# MainBoard_V1_1.net
KiCad netlist of a schematic drawn in EAGLE
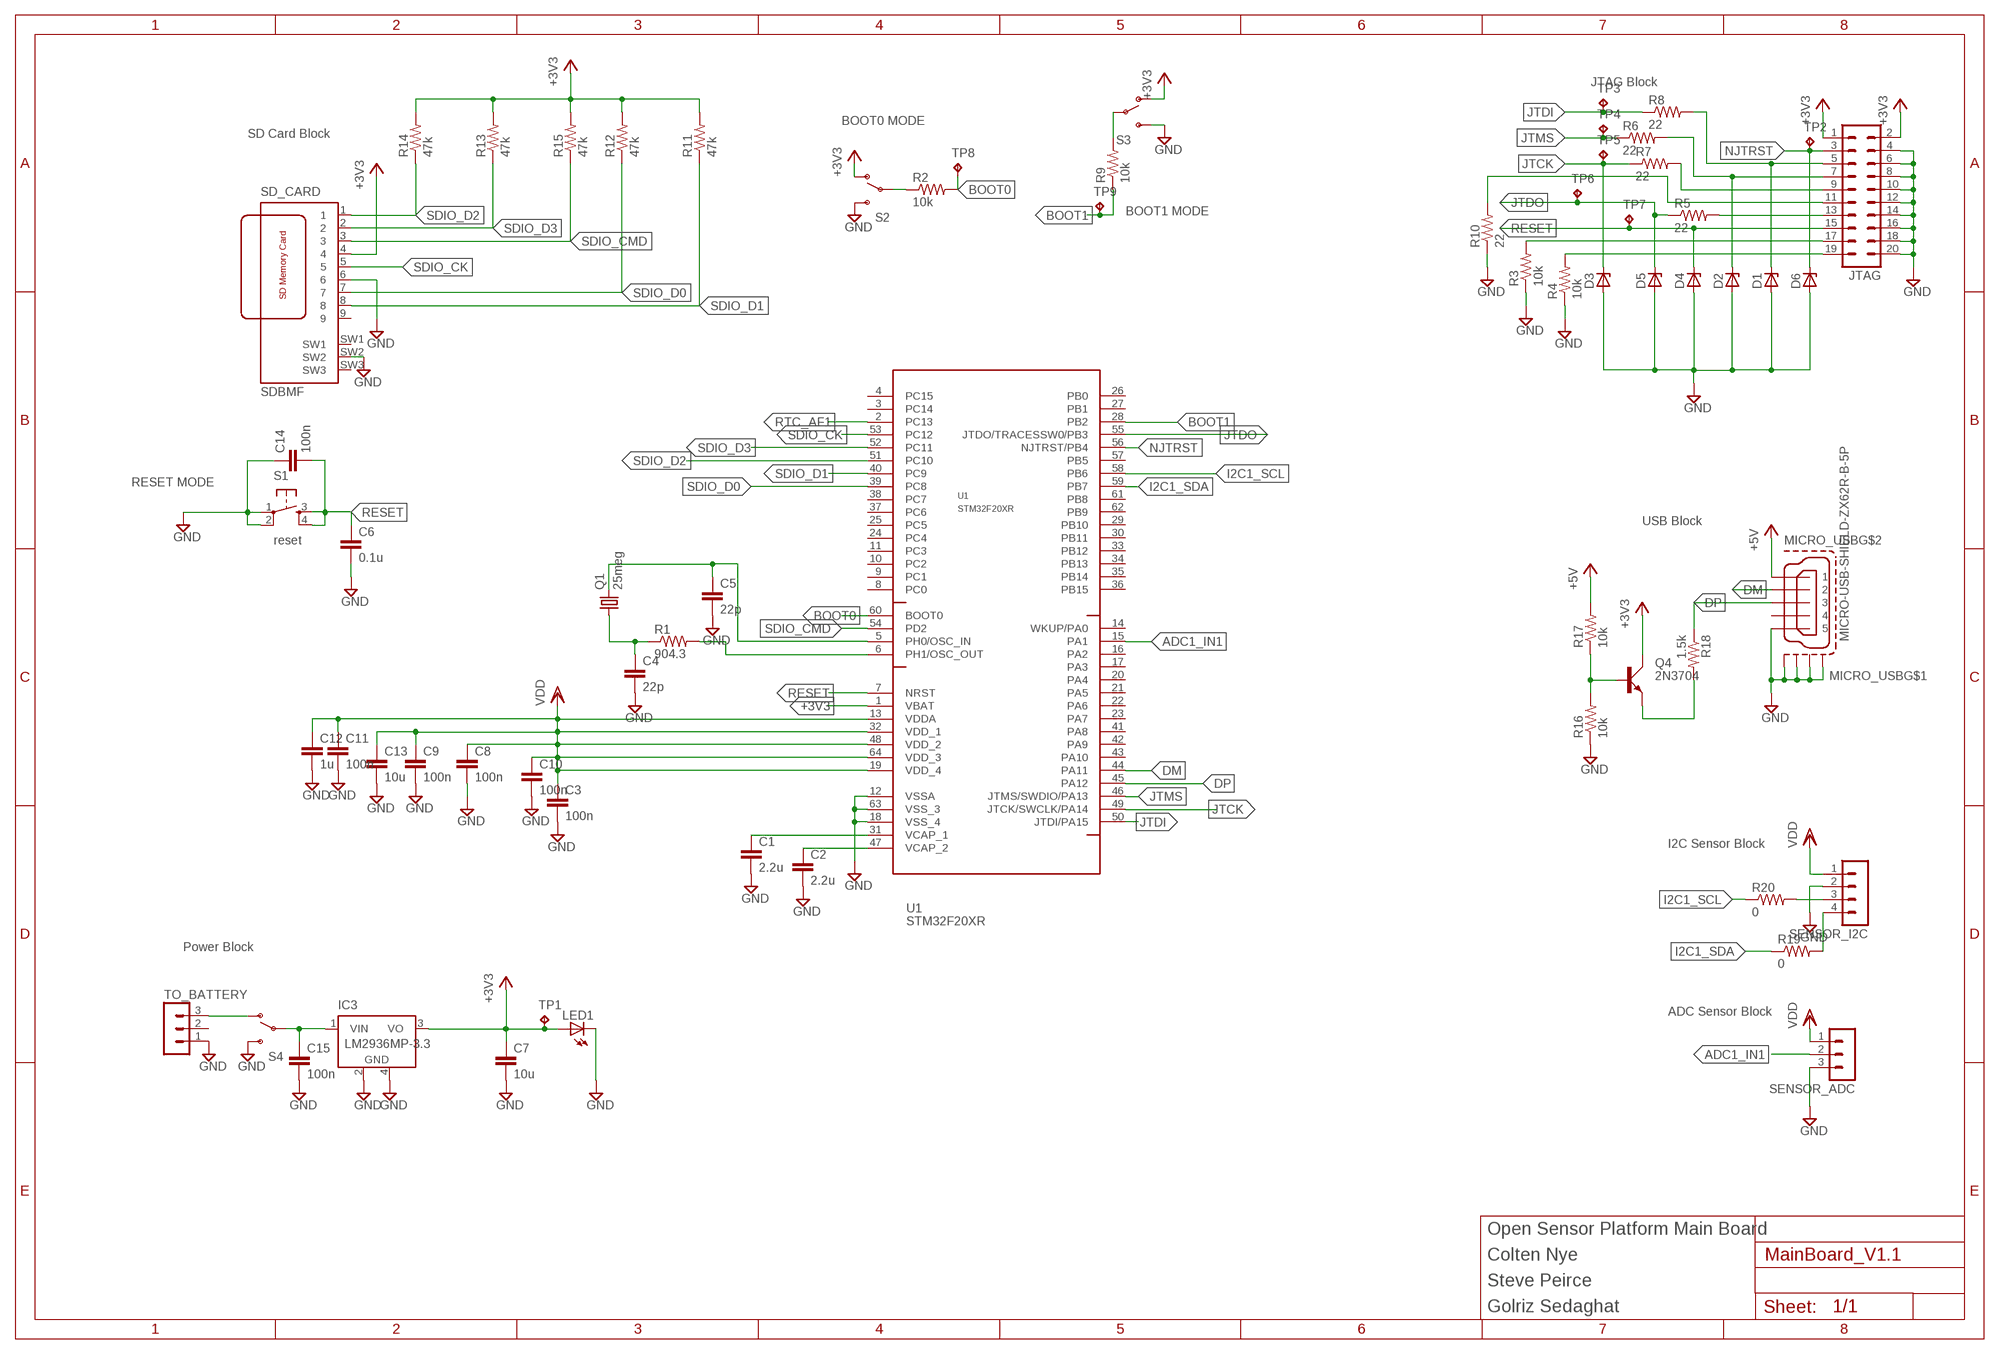
[diagram p0: schematic, sheet 1]

(export (version "E")
  (design (tool "Eeschema 10.0.6"))
  (components
    (comp (ref "C1")
      (value "2.2u")
      (footprint "eagle-import:C0805")
      (libsource (lib "eagle-import") (part "C-EUC0805"))
    )
    (comp (ref "C2")
      (value "2.2u")
      (footprint "eagle-import:C0805")
      (libsource (lib "eagle-import") (part "C-EUC0805"))
    )
    (comp (ref "C3")
      (value "100n")
      (footprint "eagle-import:C0805")
      (libsource (lib "eagle-import") (part "C-EUC0805"))
    )
    (comp (ref "C4")
      (value "22p")
      (footprint "eagle-import:C0805")
      (libsource (lib "eagle-import") (part "C-EUC0805"))
    )
    (comp (ref "C5")
      (value "22p")
      (footprint "eagle-import:C0805")
      (libsource (lib "eagle-import") (part "C-EUC0805"))
    )
    (comp (ref "C6")
      (value "0.1u")
      (footprint "eagle-import:C0805")
      (libsource (lib "eagle-import") (part "C-EUC0805"))
    )
    (comp (ref "C7")
      (value "10u")
      (footprint "eagle-import:C0805")
      (libsource (lib "eagle-import") (part "C-EUC0805"))
    )
    (comp (ref "C8")
      (value "100n")
      (footprint "eagle-import:C0805")
      (libsource (lib "eagle-import") (part "C-EUC0805"))
    )
    (comp (ref "C9")
      (value "100n")
      (footprint "eagle-import:C0805")
      (libsource (lib "eagle-import") (part "C-EUC0805"))
    )
    (comp (ref "C10")
      (value "100n")
      (footprint "eagle-import:C0805")
      (libsource (lib "eagle-import") (part "C-EUC0805"))
    )
    (comp (ref "C11")
      (value "100n")
      (footprint "eagle-import:C0805")
      (libsource (lib "eagle-import") (part "C-EUC0805"))
    )
    (comp (ref "C12")
      (value "1u")
      (footprint "eagle-import:C0805")
      (libsource (lib "eagle-import") (part "C-EUC0805"))
    )
    (comp (ref "C13")
      (value "10u")
      (footprint "eagle-import:C0805")
      (libsource (lib "eagle-import") (part "C-EUC0805"))
    )
    (comp (ref "C14")
      (value "100n")
      (footprint "eagle-import:C0805")
      (libsource (lib "eagle-import") (part "C-EUC0805"))
    )
    (comp (ref "C15")
      (value "100n")
      (footprint "eagle-import:C0805")
      (libsource (lib "eagle-import") (part "C-EUC0805"))
    )
    (comp (ref "D1")
      (value "ZENER-DIODEZD-5")
      (footprint "eagle-import:ZDIO-5")
      (libsource (lib "eagle-import") (part "ZENER-DIODEZD-5"))
    )
    (comp (ref "D2")
      (value "ZENER-DIODEZD-5")
      (footprint "eagle-import:ZDIO-5")
      (libsource (lib "eagle-import") (part "ZENER-DIODEZD-5"))
    )
    (comp (ref "D3")
      (value "ZENER-DIODEZD-5")
      (footprint "eagle-import:ZDIO-5")
      (libsource (lib "eagle-import") (part "ZENER-DIODEZD-5"))
    )
    (comp (ref "D4")
      (value "ZENER-DIODEZD-5")
      (footprint "eagle-import:ZDIO-5")
      (libsource (lib "eagle-import") (part "ZENER-DIODEZD-5"))
    )
    (comp (ref "D5")
      (value "ZENER-DIODEZD-5")
      (footprint "eagle-import:ZDIO-5")
      (libsource (lib "eagle-import") (part "ZENER-DIODEZD-5"))
    )
    (comp (ref "D6")
      (value "ZENER-DIODEZD-5")
      (footprint "eagle-import:ZDIO-5")
      (libsource (lib "eagle-import") (part "ZENER-DIODEZD-5"))
    )
    (comp (ref "IC3")
      (value "LM2936MP-3.3")
      (footprint "eagle-import:SOT223")
      (fields (field (name "MF") "NATIONAL SEMICONDUCTOR") (field (name "MPN") "LM2936MP-3.3/NOPB"))
      (libsource (lib "eagle-import") (part "LM2936MP?-3.3"))
    )
    (comp (ref "JTAG")
      (value "MA10-2")
      (footprint "eagle-import:MA10-2")
      (libsource (lib "eagle-import") (part "MA10-2"))
    )
    (comp (ref "LED1")
      (value "LEDSML0805")
      (footprint "eagle-import:SML0805")
      (libsource (lib "eagle-import") (part "LEDSML0805"))
    )
    (comp (ref "MICRO_USB")
      (value "MICRO-USB-SHIELD-ZX62R-B-5P")
      (footprint "eagle-import:ZX62R-B-5P")
      (libsource (lib "eagle-import") (part "MICRO-USB-SHIELD-ZX62R-B-5P"))
    )
    (comp (ref "Q1")
      (value "25meg")
      (footprint "eagle-import:HC49_S")
      (libsource (lib "eagle-import") (part "CRYSTALHC49S"))
    )
    (comp (ref "Q4")
      (value "2N3704")
      (footprint "eagle-import:TO92C")
      (libsource (lib "eagle-import") (part "2N3704"))
    )
    (comp (ref "R1")
      (value "904.3")
      (footprint "eagle-import:R0805")
      (libsource (lib "eagle-import") (part "R-US_R0805"))
    )
    (comp (ref "R2")
      (value "10k")
      (footprint "eagle-import:R0805")
      (libsource (lib "eagle-import") (part "R-US_R0805"))
    )
    (comp (ref "R3")
      (value "10k")
      (footprint "eagle-import:R0805")
      (libsource (lib "eagle-import") (part "R-US_R0805"))
    )
    (comp (ref "R4")
      (value "10k")
      (footprint "eagle-import:R0805")
      (libsource (lib "eagle-import") (part "R-US_R0805"))
    )
    (comp (ref "R5")
      (value "22")
      (footprint "eagle-import:R0805")
      (libsource (lib "eagle-import") (part "R-US_R0805"))
    )
    (comp (ref "R6")
      (value "22")
      (footprint "eagle-import:R0805")
      (libsource (lib "eagle-import") (part "R-US_R0805"))
    )
    (comp (ref "R7")
      (value "22")
      (footprint "eagle-import:R0805")
      (libsource (lib "eagle-import") (part "R-US_R0805"))
    )
    (comp (ref "R8")
      (value "22")
      (footprint "eagle-import:R0805")
      (libsource (lib "eagle-import") (part "R-US_R0805"))
    )
    (comp (ref "R9")
      (value "10k")
      (footprint "eagle-import:R0805")
      (libsource (lib "eagle-import") (part "R-US_R0805"))
    )
    (comp (ref "R10")
      (value "22")
      (footprint "eagle-import:R0805")
      (libsource (lib "eagle-import") (part "R-US_R0805"))
    )
    (comp (ref "R11")
      (value "47k")
      (footprint "eagle-import:R0805")
      (libsource (lib "eagle-import") (part "R-US_R0805"))
    )
    (comp (ref "R12")
      (value "47k")
      (footprint "eagle-import:R0805")
      (libsource (lib "eagle-import") (part "R-US_R0805"))
    )
    (comp (ref "R13")
      (value "47k")
      (footprint "eagle-import:R0805")
      (libsource (lib "eagle-import") (part "R-US_R0805"))
    )
    (comp (ref "R14")
      (value "47k")
      (footprint "eagle-import:R0805")
      (libsource (lib "eagle-import") (part "R-US_R0805"))
    )
    (comp (ref "R15")
      (value "47k")
      (footprint "eagle-import:R0805")
      (libsource (lib "eagle-import") (part "R-US_R0805"))
    )
    (comp (ref "R16")
      (value "10k")
      (footprint "eagle-import:R0805")
      (libsource (lib "eagle-import") (part "R-US_R0805"))
    )
    (comp (ref "R17")
      (value "10k")
      (footprint "eagle-import:R0805")
      (libsource (lib "eagle-import") (part "R-US_R0805"))
    )
    (comp (ref "R18")
      (value "1.5k")
      (footprint "eagle-import:R0805")
      (libsource (lib "eagle-import") (part "R-US_R0805"))
    )
    (comp (ref "R19")
      (value "0")
      (footprint "eagle-import:R0805")
      (libsource (lib "eagle-import") (part "R-US_R0805"))
    )
    (comp (ref "R20")
      (value "0")
      (footprint "eagle-import:R0805")
      (libsource (lib "eagle-import") (part "R-US_R0805"))
    )
    (comp (ref "S1")
      (value "reset")
      (footprint "eagle-import:TACTILE-SWITCH-SMD")
      (libsource (lib "eagle-import") (part "TAC_SWITCHSMD"))
    )
    (comp (ref "S2")
      (value "SWITCH-SPDT-SMD-A")
      (footprint "eagle-import:SWITCH-SPST-SMD-A")
      (libsource (lib "eagle-import") (part "SWITCH-SPDT-SMD-A"))
    )
    (comp (ref "S3")
      (value "SWITCH-SPDT-SMD-A")
      (footprint "eagle-import:SWITCH-SPST-SMD-A")
      (libsource (lib "eagle-import") (part "SWITCH-SPDT-SMD-A"))
    )
    (comp (ref "S4")
      (value "SWITCH-SPDT-SMD-A")
      (footprint "eagle-import:SWITCH-SPST-SMD-A")
      (libsource (lib "eagle-import") (part "SWITCH-SPDT-SMD-A"))
    )
    (comp (ref "SD_CARD")
      (value "SDBMF")
      (footprint "eagle-import:SDBMF-009XXBXX2")
      (libsource (lib "eagle-import") (part "SDBMF"))
    )
    (comp (ref "SENSOR_ADC")
      (value "MA03-1")
      (footprint "eagle-import:MA03-1")
      (libsource (lib "eagle-import") (part "MA03-1"))
    )
    (comp (ref "SENSOR_I2C")
      (value "MA04-1")
      (footprint "eagle-import:MA04-1")
      (libsource (lib "eagle-import") (part "MA04-1"))
    )
    (comp (ref "TO_BATTERY")
      (value "MA03-1")
      (footprint "eagle-import:MA03-1")
      (libsource (lib "eagle-import") (part "MA03-1"))
    )
    (comp (ref "TP1")
      (value "TPB1,27")
      (footprint "eagle-import:B1,27")
      (libsource (lib "eagle-import") (part "TPB1,27"))
    )
    (comp (ref "TP2")
      (value "TPB1,27")
      (footprint "eagle-import:B1,27")
      (libsource (lib "eagle-import") (part "TPB1,27"))
    )
    (comp (ref "TP3")
      (value "TPB1,27")
      (footprint "eagle-import:B1,27")
      (libsource (lib "eagle-import") (part "TPB1,27"))
    )
    (comp (ref "TP4")
      (value "TPB1,27")
      (footprint "eagle-import:B1,27")
      (libsource (lib "eagle-import") (part "TPB1,27"))
    )
    (comp (ref "TP5")
      (value "TPB1,27")
      (footprint "eagle-import:B1,27")
      (libsource (lib "eagle-import") (part "TPB1,27"))
    )
    (comp (ref "TP6")
      (value "TPB1,27")
      (footprint "eagle-import:B1,27")
      (libsource (lib "eagle-import") (part "TPB1,27"))
    )
    (comp (ref "TP7")
      (value "TPB1,27")
      (footprint "eagle-import:B1,27")
      (libsource (lib "eagle-import") (part "TPB1,27"))
    )
    (comp (ref "TP8")
      (value "TPB1,27")
      (footprint "eagle-import:B1,27")
      (libsource (lib "eagle-import") (part "TPB1,27"))
    )
    (comp (ref "TP9")
      (value "TPB1,27")
      (footprint "eagle-import:B1,27")
      (libsource (lib "eagle-import") (part "TPB1,27"))
    )
    (comp (ref "U1")
      (value "STM32F20XR")
      (footprint "eagle-import:LQFP64")
      (libsource (lib "eagle-import") (part "STM32F20XR"))
    )
  )
  (nets
    (net (code "1") (name "+3V3") (class "Default")
      (node (ref "C7") (pin "1") (pinfunction "1_1") (pintype "passive"))
      (node (ref "IC3") (pin "3") (pinfunction "VO_3") (pintype "passive"))
      (node (ref "JTAG") (pin "1") (pinfunction "1_1") (pintype "passive"))
      (node (ref "JTAG") (pin "2") (pinfunction "2_2") (pintype "passive"))
      (node (ref "LED1") (pin "A") (pinfunction "A_A") (pintype "passive"))
      (node (ref "Q4") (pin "C") (pinfunction "C_C") (pintype "passive"))
      (node (ref "R11") (pin "2") (pinfunction "2_2") (pintype "passive"))
      (node (ref "R12") (pin "2") (pinfunction "2_2") (pintype "passive"))
      (node (ref "R13") (pin "2") (pinfunction "2_2") (pintype "passive"))
      (node (ref "R14") (pin "2") (pinfunction "2_2") (pintype "passive"))
      (node (ref "R15") (pin "2") (pinfunction "2_2") (pintype "passive"))
      (node (ref "S2") (pin "1") (pinfunction "O_1") (pintype "passive"))
      (node (ref "S3") (pin "1") (pinfunction "O_1") (pintype "passive"))
      (node (ref "SD_CARD") (pin "4") (pinfunction "4_4") (pintype "passive"))
      (node (ref "TP1") (pin "TP") (pinfunction "TP_TP") (pintype "input"))
      (node (ref "U1") (pin "1") (pinfunction "VBAT_1") (pintype "power_in"))
    )
    (net (code "2") (name "+5V") (class "Default")
      (node (ref "MICRO_USB") (pin "1") (pinfunction "1_1") (pintype "input"))
      (node (ref "R17") (pin "2") (pinfunction "2_2") (pintype "passive"))
    )
    (net (code "3") (name "ADC1_IN1") (class "Default")
      (node (ref "SENSOR_ADC") (pin "2") (pinfunction "2_2") (pintype "passive"))
      (node (ref "U1") (pin "15") (pinfunction "PA1_15") (pintype "bidirectional"))
    )
    (net (code "4") (name "BOOT0") (class "Default")
      (node (ref "R2") (pin "2") (pinfunction "2_2") (pintype "passive"))
      (node (ref "TP8") (pin "TP") (pinfunction "TP_TP") (pintype "input"))
      (node (ref "U1") (pin "60") (pinfunction "BOOT0_60") (pintype "bidirectional"))
    )
    (net (code "5") (name "BOOT1") (class "Default")
      (node (ref "R9") (pin "1") (pinfunction "1_1") (pintype "passive"))
      (node (ref "TP9") (pin "TP") (pinfunction "TP_TP") (pintype "input"))
      (node (ref "U1") (pin "28") (pinfunction "PB2_28") (pintype "bidirectional"))
    )
    (net (code "6") (name "DM") (class "Default")
      (node (ref "MICRO_USB") (pin "2") (pinfunction "2_2") (pintype "input"))
      (node (ref "U1") (pin "44") (pinfunction "PA11_44") (pintype "bidirectional"))
    )
    (net (code "7") (name "DP") (class "Default")
      (node (ref "MICRO_USB") (pin "3") (pinfunction "3_3") (pintype "input"))
      (node (ref "R18") (pin "1") (pinfunction "1_1") (pintype "passive"))
      (node (ref "U1") (pin "45") (pinfunction "PA12_45") (pintype "bidirectional"))
    )
    (net (code "8") (name "GND") (class "Default")
      (node (ref "C1") (pin "2") (pinfunction "2_2") (pintype "passive"))
      (node (ref "C10") (pin "2") (pinfunction "2_2") (pintype "passive"))
      (node (ref "C11") (pin "2") (pinfunction "2_2") (pintype "passive"))
      (node (ref "C12") (pin "2") (pinfunction "2_2") (pintype "passive"))
      (node (ref "C13") (pin "2") (pinfunction "2_2") (pintype "passive"))
      (node (ref "C14") (pin "1") (pinfunction "1_1") (pintype "passive"))
      (node (ref "C15") (pin "2") (pinfunction "2_2") (pintype "passive"))
      (node (ref "C2") (pin "2") (pinfunction "2_2") (pintype "passive"))
      (node (ref "C3") (pin "2") (pinfunction "2_2") (pintype "passive"))
      (node (ref "C4") (pin "2") (pinfunction "2_2") (pintype "passive"))
      (node (ref "C5") (pin "2") (pinfunction "2_2") (pintype "passive"))
      (node (ref "C6") (pin "2") (pinfunction "2_2") (pintype "passive"))
      (node (ref "C7") (pin "2") (pinfunction "2_2") (pintype "passive"))
      (node (ref "C8") (pin "2") (pinfunction "2_2") (pintype "passive"))
      (node (ref "C9") (pin "2") (pinfunction "2_2") (pintype "passive"))
      (node (ref "D1") (pin "A") (pinfunction "A_A") (pintype "passive"))
      (node (ref "D2") (pin "A") (pinfunction "A_A") (pintype "passive"))
      (node (ref "D3") (pin "A") (pinfunction "A_A") (pintype "passive"))
      (node (ref "D4") (pin "A") (pinfunction "A_A") (pintype "passive"))
      (node (ref "D5") (pin "A") (pinfunction "A_A") (pintype "passive"))
      (node (ref "D6") (pin "A") (pinfunction "A_A") (pintype "passive"))
      (node (ref "IC3") (pin "2") (pinfunction "GND_2") (pintype "passive"))
      (node (ref "IC3") (pin "4") (pinfunction "GND_4") (pintype "passive"))
      (node (ref "JTAG") (pin "10") (pinfunction "10_10") (pintype "passive"))
      (node (ref "JTAG") (pin "12") (pinfunction "12_12") (pintype "passive"))
      (node (ref "JTAG") (pin "14") (pinfunction "14_14") (pintype "passive"))
      (node (ref "JTAG") (pin "16") (pinfunction "16_16") (pintype "passive"))
      (node (ref "JTAG") (pin "18") (pinfunction "18_18") (pintype "passive"))
      (node (ref "JTAG") (pin "20") (pinfunction "20_20") (pintype "passive"))
      (node (ref "JTAG") (pin "4") (pinfunction "4_4") (pintype "passive"))
      (node (ref "JTAG") (pin "6") (pinfunction "6_6") (pintype "passive"))
      (node (ref "JTAG") (pin "8") (pinfunction "8_8") (pintype "passive"))
      (node (ref "LED1") (pin "C") (pinfunction "C_C") (pintype "passive"))
      (node (ref "MICRO_USB") (pin "5") (pinfunction "5_5") (pintype "input"))
      (node (ref "MICRO_USB") (pin "M1") (pinfunction "S1_M1") (pintype "passive"))
      (node (ref "MICRO_USB") (pin "M2") (pinfunction "S2_M2") (pintype "passive"))
      (node (ref "MICRO_USB") (pin "M3") (pinfunction "S3_M3") (pintype "passive"))
      (node (ref "MICRO_USB") (pin "M4") (pinfunction "S4_M4") (pintype "passive"))
      (node (ref "R10") (pin "1") (pinfunction "1_1") (pintype "passive"))
      (node (ref "R16") (pin "1") (pinfunction "1_1") (pintype "passive"))
      (node (ref "R3") (pin "1") (pinfunction "1_1") (pintype "passive"))
      (node (ref "R4") (pin "1") (pinfunction "1_1") (pintype "passive"))
      (node (ref "S1") (pin "1") (pinfunction "1_1") (pintype "passive"))
      (node (ref "S1") (pin "2") (pinfunction "2_2") (pintype "passive"))
      (node (ref "S2") (pin "3") (pinfunction "S_3") (pintype "passive"))
      (node (ref "S3") (pin "3") (pinfunction "S_3") (pintype "passive"))
      (node (ref "S4") (pin "3") (pinfunction "S_3") (pintype "passive"))
      (node (ref "SD_CARD") (pin "6") (pinfunction "6_6") (pintype "passive"))
      (node (ref "SD_CARD") (pin "SW2") (pinfunction "SW2_SW2") (pintype "passive"))
      (node (ref "SENSOR_ADC") (pin "3") (pinfunction "3_3") (pintype "passive"))
      (node (ref "SENSOR_I2C") (pin "2") (pinfunction "2_2") (pintype "passive"))
      (node (ref "TO_BATTERY") (pin "1") (pinfunction "1_1") (pintype "passive"))
      (node (ref "U1") (pin "12") (pinfunction "VSSA_12") (pintype "power_in"))
      (node (ref "U1") (pin "18") (pinfunction "VSS_4_18") (pintype "power_in"))
      (node (ref "U1") (pin "63") (pinfunction "VSS_3_63") (pintype "power_in"))
    )
    (net (code "9") (name "I2C1_SCL") (class "Default")
      (node (ref "R20") (pin "1") (pinfunction "1_1") (pintype "passive"))
      (node (ref "U1") (pin "58") (pinfunction "PB6_58") (pintype "bidirectional"))
    )
    (net (code "10") (name "I2C1_SDA") (class "Default")
      (node (ref "R19") (pin "1") (pinfunction "1_1") (pintype "passive"))
      (node (ref "U1") (pin "59") (pinfunction "PB7_59") (pintype "bidirectional"))
    )
    (net (code "11") (name "JTCK") (class "Default")
      (node (ref "D3") (pin "C") (pinfunction "C_C") (pintype "passive"))
      (node (ref "R7") (pin "1") (pinfunction "1_1") (pintype "passive"))
      (node (ref "TP5") (pin "TP") (pinfunction "TP_TP") (pintype "input"))
      (node (ref "U1") (pin "49") (pinfunction "JTCK/SWCLK/PA14_49") (pintype "bidirectional"))
    )
    (net (code "12") (name "JTDI") (class "Default")
      (node (ref "R8") (pin "1") (pinfunction "1_1") (pintype "passive"))
      (node (ref "TP3") (pin "TP") (pinfunction "TP_TP") (pintype "input"))
      (node (ref "U1") (pin "50") (pinfunction "JTDI/PA15_50") (pintype "bidirectional"))
    )
    (net (code "13") (name "JTDO") (class "Default")
      (node (ref "D5") (pin "C") (pinfunction "C_C") (pintype "passive"))
      (node (ref "R5") (pin "1") (pinfunction "1_1") (pintype "passive"))
      (node (ref "TP6") (pin "TP") (pinfunction "TP_TP") (pintype "input"))
      (node (ref "U1") (pin "55") (pinfunction "JTDO/TRACESSW0/PB3_55") (pintype "bidirectional"))
    )
    (net (code "14") (name "JTMS") (class "Default")
      (node (ref "R6") (pin "1") (pinfunction "1_1") (pintype "passive"))
      (node (ref "TP4") (pin "TP") (pinfunction "TP_TP") (pintype "input"))
      (node (ref "U1") (pin "46") (pinfunction "JTMS/SWDIO/PA13_46") (pintype "bidirectional"))
    )
    (net (code "15") (name "NJTRST") (class "Default")
      (node (ref "D6") (pin "C") (pinfunction "C_C") (pintype "passive"))
      (node (ref "JTAG") (pin "3") (pinfunction "3_3") (pintype "passive"))
      (node (ref "TP2") (pin "TP") (pinfunction "TP_TP") (pintype "input"))
      (node (ref "U1") (pin "56") (pinfunction "NJTRST/PB4_56") (pintype "bidirectional"))
    )
    (net (code "16") (name "Net-(C4-Pad1)") (class "Default")
      (node (ref "C4") (pin "1") (pinfunction "1_1") (pintype "passive"))
      (node (ref "Q1") (pin "1") (pinfunction "1_1") (pintype "passive"))
      (node (ref "R1") (pin "1") (pinfunction "1_1") (pintype "passive"))
    )
    (net (code "17") (name "Net-(D1-PadC)") (class "Default")
      (node (ref "D1") (pin "C") (pinfunction "C_C") (pintype "passive"))
      (node (ref "JTAG") (pin "5") (pinfunction "5_5") (pintype "passive"))
      (node (ref "R8") (pin "2") (pinfunction "2_2") (pintype "passive"))
    )
    (net (code "18") (name "Net-(D2-PadC)") (class "Default")
      (node (ref "D2") (pin "C") (pinfunction "C_C") (pintype "passive"))
      (node (ref "JTAG") (pin "7") (pinfunction "7_7") (pintype "passive"))
      (node (ref "R6") (pin "2") (pinfunction "2_2") (pintype "passive"))
    )
    (net (code "19") (name "Net-(IC3-VIN)") (class "Default")
      (node (ref "C15") (pin "1") (pinfunction "1_1") (pintype "passive"))
      (node (ref "IC3") (pin "1") (pinfunction "VIN_1") (pintype "input"))
      (node (ref "S4") (pin "2") (pinfunction "P_2") (pintype "passive"))
    )
    (net (code "20") (name "Net-(JTAG-Pad9)") (class "Default")
      (node (ref "JTAG") (pin "9") (pinfunction "9_9") (pintype "passive"))
      (node (ref "R7") (pin "2") (pinfunction "2_2") (pintype "passive"))
    )
    (net (code "21") (name "Net-(JTAG-Pad11)") (class "Default")
      (node (ref "JTAG") (pin "11") (pinfunction "11_11") (pintype "passive"))
      (node (ref "R10") (pin "2") (pinfunction "2_2") (pintype "passive"))
    )
    (net (code "22") (name "Net-(JTAG-Pad13)") (class "Default")
      (node (ref "JTAG") (pin "13") (pinfunction "13_13") (pintype "passive"))
      (node (ref "R5") (pin "2") (pinfunction "2_2") (pintype "passive"))
    )
    (net (code "23") (name "Net-(JTAG-Pad17)") (class "Default")
      (node (ref "JTAG") (pin "17") (pinfunction "17_17") (pintype "passive"))
      (node (ref "R3") (pin "2") (pinfunction "2_2") (pintype "passive"))
    )
    (net (code "24") (name "Net-(JTAG-Pad19)") (class "Default")
      (node (ref "JTAG") (pin "19") (pinfunction "19_19") (pintype "passive"))
      (node (ref "R4") (pin "2") (pinfunction "2_2") (pintype "passive"))
    )
    (net (code "25") (name "Net-(Q4-PadB)") (class "Default")
      (node (ref "Q4") (pin "B") (pinfunction "B_B") (pintype "passive"))
      (node (ref "R16") (pin "2") (pinfunction "2_2") (pintype "passive"))
      (node (ref "R17") (pin "1") (pinfunction "1_1") (pintype "passive"))
    )
    (net (code "26") (name "Net-(Q4-PadE)") (class "Default")
      (node (ref "Q4") (pin "E") (pinfunction "E_E") (pintype "passive"))
      (node (ref "R18") (pin "2") (pinfunction "2_2") (pintype "passive"))
    )
    (net (code "27") (name "Net-(R19-Pad2)") (class "Default")
      (node (ref "R19") (pin "2") (pinfunction "2_2") (pintype "passive"))
      (node (ref "SENSOR_I2C") (pin "4") (pinfunction "4_4") (pintype "passive"))
    )
    (net (code "28") (name "Net-(R20-Pad2)") (class "Default")
      (node (ref "R20") (pin "2") (pinfunction "2_2") (pintype "passive"))
      (node (ref "SENSOR_I2C") (pin "3") (pinfunction "3_3") (pintype "passive"))
    )
    (net (code "29") (name "Net-(S2-P)") (class "Default")
      (node (ref "R2") (pin "1") (pinfunction "1_1") (pintype "passive"))
      (node (ref "S2") (pin "2") (pinfunction "P_2") (pintype "passive"))
    )
    (net (code "30") (name "Net-(S3-P)") (class "Default")
      (node (ref "R9") (pin "2") (pinfunction "2_2") (pintype "passive"))
      (node (ref "S3") (pin "2") (pinfunction "P_2") (pintype "passive"))
    )
    (net (code "31") (name "Net-(S4-O)") (class "Default")
      (node (ref "S4") (pin "1") (pinfunction "O_1") (pintype "passive"))
      (node (ref "TO_BATTERY") (pin "3") (pinfunction "3_3") (pintype "passive"))
    )
    (net (code "32") (name "Net-(U1-PH0{slash}OSC_IN)") (class "Default")
      (node (ref "C5") (pin "1") (pinfunction "1_1") (pintype "passive"))
      (node (ref "Q1") (pin "2") (pinfunction "2_2") (pintype "passive"))
      (node (ref "U1") (pin "5") (pinfunction "PH0/OSC_IN_5") (pintype "bidirectional"))
    )
    (net (code "33") (name "Net-(U1-PH1{slash}OSC_OUT)") (class "Default")
      (node (ref "R1") (pin "2") (pinfunction "2_2") (pintype "passive"))
      (node (ref "U1") (pin "6") (pinfunction "PH1/OSC_OUT_6") (pintype "bidirectional"))
    )
    (net (code "34") (name "Net-(U1-VCAP_1)") (class "Default")
      (node (ref "C1") (pin "1") (pinfunction "1_1") (pintype "passive"))
      (node (ref "U1") (pin "31") (pinfunction "VCAP_1_31") (pintype "power_in"))
    )
    (net (code "35") (name "Net-(U1-VCAP_2)") (class "Default")
      (node (ref "C2") (pin "1") (pinfunction "1_1") (pintype "passive"))
      (node (ref "U1") (pin "47") (pinfunction "VCAP_2_47") (pintype "power_in"))
    )
    (net (code "36") (name "RESET") (class "Default")
      (node (ref "C14") (pin "2") (pinfunction "2_2") (pintype "passive"))
      (node (ref "C6") (pin "1") (pinfunction "1_1") (pintype "passive"))
      (node (ref "D4") (pin "C") (pinfunction "C_C") (pintype "passive"))
      (node (ref "JTAG") (pin "15") (pinfunction "15_15") (pintype "passive"))
      (node (ref "S1") (pin "3") (pinfunction "3_3") (pintype "passive"))
      (node (ref "S1") (pin "4") (pinfunction "4_4") (pintype "passive"))
      (node (ref "TP7") (pin "TP") (pinfunction "TP_TP") (pintype "input"))
      (node (ref "U1") (pin "7") (pinfunction "NRST_7") (pintype "power_in"))
    )
    (net (code "37") (name "RTC_AF1") (class "Default")
      (node (ref "U1") (pin "2") (pinfunction "PC13_2") (pintype "bidirectional"))
    )
    (net (code "38") (name "SDIO_CK") (class "Default")
      (node (ref "SD_CARD") (pin "5") (pinfunction "5_5") (pintype "passive"))
      (node (ref "U1") (pin "53") (pinfunction "PC12_53") (pintype "bidirectional"))
    )
    (net (code "39") (name "SDIO_CMD") (class "Default")
      (node (ref "R15") (pin "1") (pinfunction "1_1") (pintype "passive"))
      (node (ref "SD_CARD") (pin "3") (pinfunction "3_3") (pintype "passive"))
      (node (ref "U1") (pin "54") (pinfunction "PD2_54") (pintype "bidirectional"))
    )
    (net (code "40") (name "SDIO_D0") (class "Default")
      (node (ref "R12") (pin "1") (pinfunction "1_1") (pintype "passive"))
      (node (ref "SD_CARD") (pin "7") (pinfunction "7_7") (pintype "passive"))
      (node (ref "U1") (pin "39") (pinfunction "PC8_39") (pintype "bidirectional"))
    )
    (net (code "41") (name "SDIO_D1") (class "Default")
      (node (ref "R11") (pin "1") (pinfunction "1_1") (pintype "passive"))
      (node (ref "SD_CARD") (pin "8") (pinfunction "8_8") (pintype "passive"))
      (node (ref "U1") (pin "40") (pinfunction "PC9_40") (pintype "bidirectional"))
    )
    (net (code "42") (name "SDIO_D2") (class "Default")
      (node (ref "R14") (pin "1") (pinfunction "1_1") (pintype "passive"))
      (node (ref "SD_CARD") (pin "1") (pinfunction "1_1") (pintype "passive"))
      (node (ref "U1") (pin "51") (pinfunction "PC10_51") (pintype "bidirectional"))
    )
    (net (code "43") (name "SDIO_D3") (class "Default")
      (node (ref "R13") (pin "1") (pinfunction "1_1") (pintype "passive"))
      (node (ref "SD_CARD") (pin "2") (pinfunction "2_2") (pintype "passive"))
      (node (ref "U1") (pin "52") (pinfunction "PC11_52") (pintype "bidirectional"))
    )
    (net (code "44") (name "VDD") (class "Default")
      (node (ref "C10") (pin "1") (pinfunction "1_1") (pintype "passive"))
      (node (ref "C11") (pin "1") (pinfunction "1_1") (pintype "passive"))
      (node (ref "C12") (pin "1") (pinfunction "1_1") (pintype "passive"))
      (node (ref "C13") (pin "1") (pinfunction "1_1") (pintype "passive"))
      (node (ref "C3") (pin "1") (pinfunction "1_1") (pintype "passive"))
      (node (ref "C8") (pin "1") (pinfunction "1_1") (pintype "passive"))
      (node (ref "C9") (pin "1") (pinfunction "1_1") (pintype "passive"))
      (node (ref "SENSOR_ADC") (pin "1") (pinfunction "1_1") (pintype "passive"))
      (node (ref "SENSOR_I2C") (pin "1") (pinfunction "1_1") (pintype "passive"))
      (node (ref "U1") (pin "13") (pinfunction "VDDA_13") (pintype "power_in"))
      (node (ref "U1") (pin "19") (pinfunction "VDD_4_19") (pintype "power_in"))
      (node (ref "U1") (pin "32") (pinfunction "VDD_1_32") (pintype "power_in"))
      (node (ref "U1") (pin "48") (pinfunction "VDD_2_48") (pintype "power_in"))
      (node (ref "U1") (pin "64") (pinfunction "VDD_3_64") (pintype "power_in"))
    )
    (net (code "45") (name "unconnected-(MICRO_USB-Pad4)") (class "Default")
      (node (ref "MICRO_USB") (pin "4") (pinfunction "4_4") (pintype "input"))
    )
    (net (code "46") (name "unconnected-(SD_CARD-Pad9)") (class "Default")
      (node (ref "SD_CARD") (pin "9") (pinfunction "9_9") (pintype "passive"))
    )
    (net (code "47") (name "unconnected-(SD_CARD-PadSW1)") (class "Default")
      (node (ref "SD_CARD") (pin "SW1") (pinfunction "SW1_SW1") (pintype "passive"))
    )
    (net (code "48") (name "unconnected-(SD_CARD-PadSW3)") (class "Default")
      (node (ref "SD_CARD") (pin "SW3") (pinfunction "SW3_SW3") (pintype "passive"))
    )
    (net (code "49") (name "unconnected-(TO_BATTERY-Pad2)") (class "Default")
      (node (ref "TO_BATTERY") (pin "2") (pinfunction "2_2") (pintype "passive"))
    )
    (net (code "50") (name "unconnected-(U1-PA2-Pad16)") (class "Default")
      (node (ref "U1") (pin "16") (pinfunction "PA2_16") (pintype "bidirectional"))
    )
    (net (code "51") (name "unconnected-(U1-PA3-Pad17)") (class "Default")
      (node (ref "U1") (pin "17") (pinfunction "PA3_17") (pintype "bidirectional"))
    )
    (net (code "52") (name "unconnected-(U1-PA4-Pad20)") (class "Default")
      (node (ref "U1") (pin "20") (pinfunction "PA4_20") (pintype "bidirectional"))
    )
    (net (code "53") (name "unconnected-(U1-PA5-Pad21)") (class "Default")
      (node (ref "U1") (pin "21") (pinfunction "PA5_21") (pintype "bidirectional"))
    )
    (net (code "54") (name "unconnected-(U1-PA6-Pad22)") (class "Default")
      (node (ref "U1") (pin "22") (pinfunction "PA6_22") (pintype "bidirectional"))
    )
    (net (code "55") (name "unconnected-(U1-PA7-Pad23)") (class "Default")
      (node (ref "U1") (pin "23") (pinfunction "PA7_23") (pintype "bidirectional"))
    )
    (net (code "56") (name "unconnected-(U1-PA8-Pad41)") (class "Default")
      (node (ref "U1") (pin "41") (pinfunction "PA8_41") (pintype "bidirectional"))
    )
    (net (code "57") (name "unconnected-(U1-PA9-Pad42)") (class "Default")
      (node (ref "U1") (pin "42") (pinfunction "PA9_42") (pintype "bidirectional"))
    )
    (net (code "58") (name "unconnected-(U1-PA10-Pad43)") (class "Default")
      (node (ref "U1") (pin "43") (pinfunction "PA10_43") (pintype "bidirectional"))
    )
    (net (code "59") (name "unconnected-(U1-PB0-Pad26)") (class "Default")
      (node (ref "U1") (pin "26") (pinfunction "PB0_26") (pintype "bidirectional"))
    )
    (net (code "60") (name "unconnected-(U1-PB1-Pad27)") (class "Default")
      (node (ref "U1") (pin "27") (pinfunction "PB1_27") (pintype "bidirectional"))
    )
    (net (code "61") (name "unconnected-(U1-PB5-Pad57)") (class "Default")
      (node (ref "U1") (pin "57") (pinfunction "PB5_57") (pintype "bidirectional"))
    )
    (net (code "62") (name "unconnected-(U1-PB8-Pad61)") (class "Default")
      (node (ref "U1") (pin "61") (pinfunction "PB8_61") (pintype "bidirectional"))
    )
    (net (code "63") (name "unconnected-(U1-PB9-Pad62)") (class "Default")
      (node (ref "U1") (pin "62") (pinfunction "PB9_62") (pintype "bidirectional"))
    )
    (net (code "64") (name "unconnected-(U1-PB10-Pad29)") (class "Default")
      (node (ref "U1") (pin "29") (pinfunction "PB10_29") (pintype "bidirectional"))
    )
    (net (code "65") (name "unconnected-(U1-PB11-Pad30)") (class "Default")
      (node (ref "U1") (pin "30") (pinfunction "PB11_30") (pintype "bidirectional"))
    )
    (net (code "66") (name "unconnected-(U1-PB12-Pad33)") (class "Default")
      (node (ref "U1") (pin "33") (pinfunction "PB12_33") (pintype "bidirectional"))
    )
    (net (code "67") (name "unconnected-(U1-PB13-Pad34)") (class "Default")
      (node (ref "U1") (pin "34") (pinfunction "PB13_34") (pintype "bidirectional"))
    )
    (net (code "68") (name "unconnected-(U1-PB14-Pad35)") (class "Default")
      (node (ref "U1") (pin "35") (pinfunction "PB14_35") (pintype "bidirectional"))
    )
    (net (code "69") (name "unconnected-(U1-PB15-Pad36)") (class "Default")
      (node (ref "U1") (pin "36") (pinfunction "PB15_36") (pintype "bidirectional"))
    )
    (net (code "70") (name "unconnected-(U1-PC0-Pad8)") (class "Default")
      (node (ref "U1") (pin "8") (pinfunction "PC0_8") (pintype "bidirectional"))
    )
    (net (code "71") (name "unconnected-(U1-PC1-Pad9)") (class "Default")
      (node (ref "U1") (pin "9") (pinfunction "PC1_9") (pintype "bidirectional"))
    )
    (net (code "72") (name "unconnected-(U1-PC2-Pad10)") (class "Default")
      (node (ref "U1") (pin "10") (pinfunction "PC2_10") (pintype "bidirectional"))
    )
    (net (code "73") (name "unconnected-(U1-PC3-Pad11)") (class "Default")
      (node (ref "U1") (pin "11") (pinfunction "PC3_11") (pintype "bidirectional"))
    )
    (net (code "74") (name "unconnected-(U1-PC4-Pad24)") (class "Default")
      (node (ref "U1") (pin "24") (pinfunction "PC4_24") (pintype "bidirectional"))
    )
    (net (code "75") (name "unconnected-(U1-PC5-Pad25)") (class "Default")
      (node (ref "U1") (pin "25") (pinfunction "PC5_25") (pintype "bidirectional"))
    )
    (net (code "76") (name "unconnected-(U1-PC6-Pad37)") (class "Default")
      (node (ref "U1") (pin "37") (pinfunction "PC6_37") (pintype "bidirectional"))
    )
    (net (code "77") (name "unconnected-(U1-PC7-Pad38)") (class "Default")
      (node (ref "U1") (pin "38") (pinfunction "PC7_38") (pintype "bidirectional"))
    )
    (net (code "78") (name "unconnected-(U1-PC14-Pad3)") (class "Default")
      (node (ref "U1") (pin "3") (pinfunction "PC14_3") (pintype "bidirectional"))
    )
    (net (code "79") (name "unconnected-(U1-PC15-Pad4)") (class "Default")
      (node (ref "U1") (pin "4") (pinfunction "PC15_4") (pintype "bidirectional"))
    )
    (net (code "80") (name "unconnected-(U1-WKUP{slash}PA0-Pad14)") (class "Default")
      (node (ref "U1") (pin "14") (pinfunction "WKUP/PA0_14") (pintype "bidirectional"))
    )
  )
)
